# xenguon.net
KiCad netlist of a schematic drawn in Altium Designer
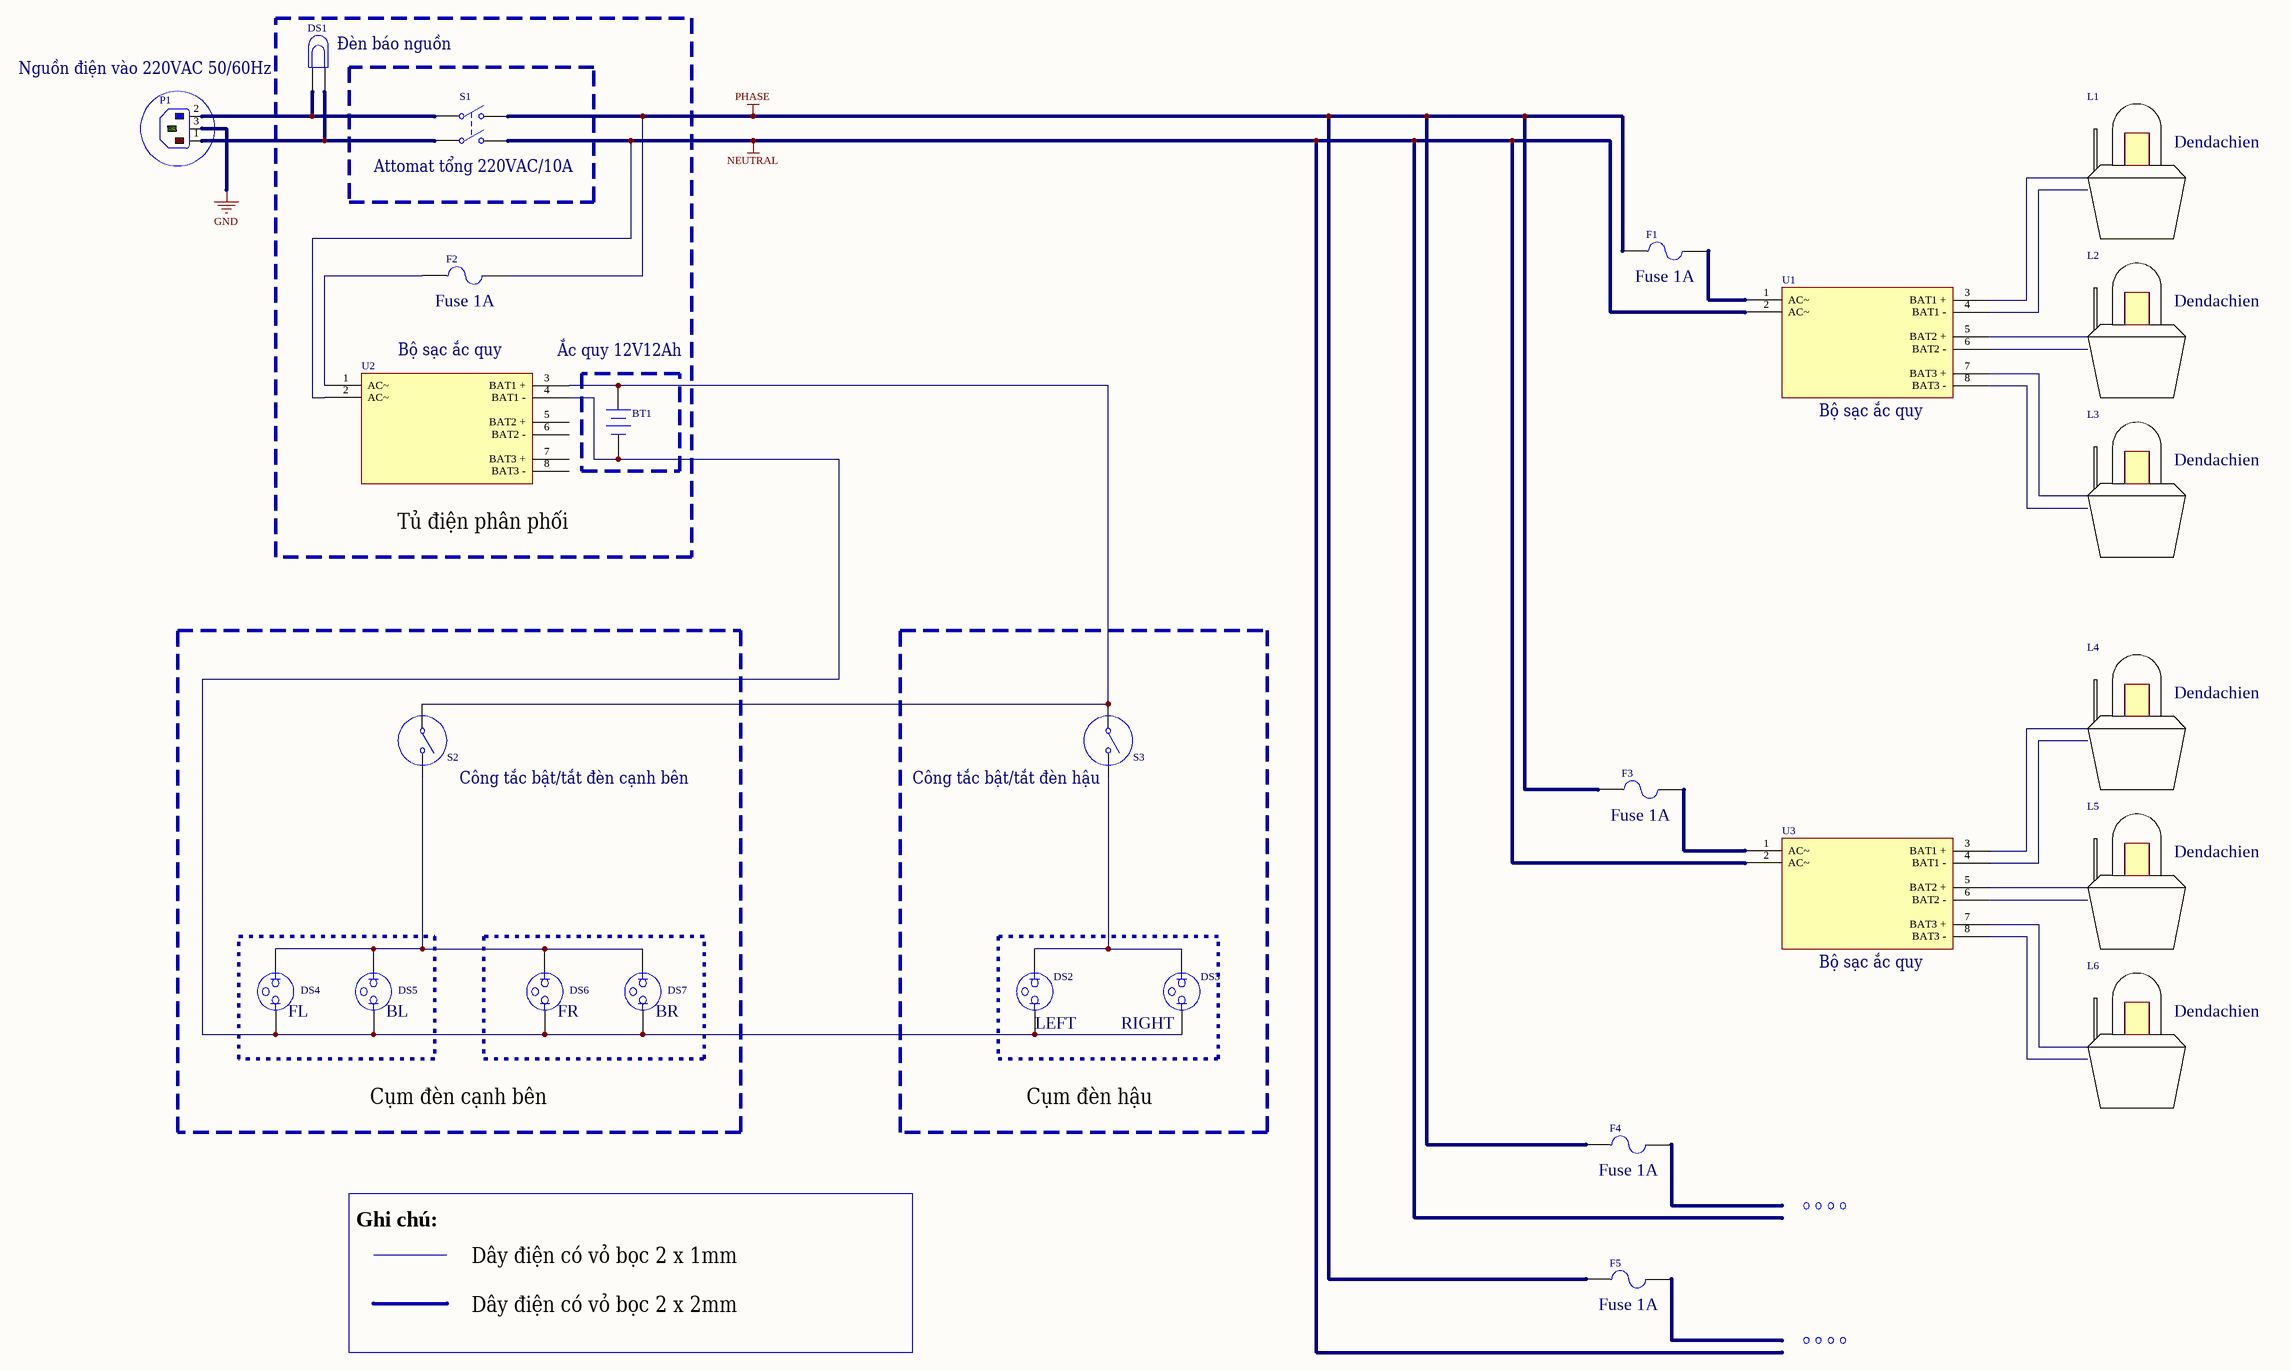
[diagram p0: xenguon.SchDoc]

(export (version "E")
  (design (tool "Eeschema 10.0.6"))
  (components
    (comp (ref "BT1")
      (value "Ắc quy 12V12Ah")
      (footprint "BAT-2")
      (description "Multicell Battery")
      (fields (field (name "PUBLISHER") "Altium Limited"))
      (libsource (lib "Miscellaneous Devices") (part "Battery"))
    )
    (comp (ref "DS1")
      (value "Đèn báo nguồn")
      (footprint "PIN2")
      (description "Incandescent Bulb")
      (fields (field (name "PUBLISHER") "Altium Limited"))
      (libsource (lib "Miscellaneous Devices") (part "Lamp"))
    )
    (comp (ref "DS2")
      (value "LEFT")
      (footprint "PIN2")
      (description "Neon Lamp")
      (fields (field (name "PUBLISHER") "Altium Limited"))
      (libsource (lib "Miscellaneous Devices") (part "Lamp Neon"))
    )
    (comp (ref "DS3")
      (value "RIGHT")
      (footprint "PIN2")
      (description "Neon Lamp")
      (fields (field (name "PUBLISHER") "Altium Limited"))
      (libsource (lib "Miscellaneous Devices") (part "Lamp Neon"))
    )
    (comp (ref "DS4")
      (value "FL")
      (footprint "PIN2")
      (description "Neon Lamp")
      (fields (field (name "PUBLISHER") "Altium Limited"))
      (libsource (lib "Miscellaneous Devices") (part "Lamp Neon"))
    )
    (comp (ref "DS5")
      (value "BL")
      (footprint "PIN2")
      (description "Neon Lamp")
      (fields (field (name "PUBLISHER") "Altium Limited"))
      (libsource (lib "Miscellaneous Devices") (part "Lamp Neon"))
    )
    (comp (ref "DS6")
      (value "FR")
      (footprint "PIN2")
      (description "Neon Lamp")
      (fields (field (name "PUBLISHER") "Altium Limited"))
      (libsource (lib "Miscellaneous Devices") (part "Lamp Neon"))
    )
    (comp (ref "DS7")
      (value "BR")
      (footprint "PIN2")
      (description "Neon Lamp")
      (fields (field (name "PUBLISHER") "Altium Limited"))
      (libsource (lib "Miscellaneous Devices") (part "Lamp Neon"))
    )
    (comp (ref "F1")
      (value "Fuse 1A")
      (footprint "PIN-W2/E2.8")
      (description "Fuse")
      (fields (field (name "PUBLISHER") "Altium Limited"))
      (libsource (lib "Miscellaneous Devices") (part "Fuse 2"))
    )
    (comp (ref "F2")
      (value "Fuse 1A")
      (footprint "PIN-W2/E2.8")
      (description "Fuse")
      (fields (field (name "PUBLISHER") "Altium Limited"))
      (libsource (lib "Miscellaneous Devices") (part "Fuse 2"))
    )
    (comp (ref "F3")
      (value "Fuse 1A")
      (footprint "PIN-W2/E2.8")
      (description "Fuse")
      (fields (field (name "PUBLISHER") "Altium Limited"))
      (libsource (lib "Miscellaneous Devices") (part "Fuse 2"))
    )
    (comp (ref "F4")
      (value "Fuse 1A")
      (footprint "PIN-W2/E2.8")
      (description "Fuse")
      (fields (field (name "PUBLISHER") "Altium Limited"))
      (libsource (lib "Miscellaneous Devices") (part "Fuse 2"))
    )
    (comp (ref "F5")
      (value "Fuse 1A")
      (footprint "PIN-W2/E2.8")
      (description "Fuse")
      (fields (field (name "PUBLISHER") "Altium Limited"))
      (libsource (lib "Miscellaneous Devices") (part "Fuse 2"))
    )
    (comp (ref "L1") (value "Dendachien") (libsource (lib "DnsSchLib") (part "Dendachien")))
    (comp (ref "L2") (value "Dendachien") (libsource (lib "DnsSchLib") (part "Dendachien")))
    (comp (ref "L3") (value "Dendachien") (libsource (lib "DnsSchLib") (part "Dendachien")))
    (comp (ref "L4") (value "Dendachien") (libsource (lib "DnsSchLib") (part "Dendachien")))
    (comp (ref "L5") (value "Dendachien") (libsource (lib "DnsSchLib") (part "Dendachien")))
    (comp (ref "L6") (value "Dendachien") (libsource (lib "DnsSchLib") (part "Dendachien")))
    (comp (ref "P1")
      (value "Nguồn điện vào 220VAC 50/60Hz")
      (footprint "IEC9.14-2H3")
      (description "IEC Mains Power Inlet, EN60 320-1 C14 Class I Cold Condition, PC Flange Rear Mount, Chassis Plug")
      (fields (field (name "PUBLISHER") "Altium Limited"))
      (libsource (lib "Miscellaneous Connectors") (part "Plug AC Male"))
    )
    (comp (ref "S1")
      (value "Attomat tổng 220VAC/10A")
      (footprint "DPST-4")
      (description "Double-Pole, Single-Throw Switch")
      (fields (field (name "PUBLISHER") "Altium Limited"))
      (libsource (lib "Miscellaneous Devices") (part "SW-DPST"))
    )
    (comp (ref "S2")
      (value "Công tắc bật/tắt đèn cạnh bên")
      (footprint "SPST-2")
      (description "Single-Pole, Single-Throw Switch")
      (fields (field (name "PUBLISHER") "Altium Limited"))
      (libsource (lib "Miscellaneous Devices") (part "SW-SPST"))
    )
    (comp (ref "S3")
      (value "Công tắc bật/tắt đèn hậu")
      (footprint "SPST-2")
      (description "Single-Pole, Single-Throw Switch")
      (fields (field (name "PUBLISHER") "Altium Limited"))
      (libsource (lib "Miscellaneous Devices") (part "SW-SPST"))
    )
    (comp (ref "U1") (value "Bộ sạc ắc quy") (libsource (lib "DnsSchLib") (part "Bosacacquy")))
    (comp (ref "U2") (value "Bộ sạc ắc quy") (libsource (lib "DnsSchLib") (part "Bosacacquy")))
    (comp (ref "U3") (value "Bộ sạc ắc quy") (libsource (lib "DnsSchLib") (part "Bosacacquy")))
  )
  (nets
    (net (code "1") (name "GND") (class "Default")
      (node (ref "P1") (pin "3") (pinfunction "E_3") (pintype "power_in"))
    )
    (net (code "2") (name "NEUTRAL") (class "Default")
      (node (ref "S1") (pin "4") (pinfunction "NO2_4") (pintype "passive"))
      (node (ref "U1") (pin "2") (pinfunction "AC~_2") (pintype "passive"))
      (node (ref "U2") (pin "2") (pinfunction "AC~_2") (pintype "passive"))
      (node (ref "U3") (pin "2") (pinfunction "AC~_2") (pintype "passive"))
    )
    (net (code "3") (name "Net-(BT1-+)") (class "Default")
      (node (ref "BT1") (pin "1") (pinfunction "+_1") (pintype "passive"))
      (node (ref "S2") (pin "1") (pinfunction "COMMON_1") (pintype "passive"))
      (node (ref "S3") (pin "1") (pinfunction "COMMON_1") (pintype "passive"))
      (node (ref "U2") (pin "3") (pinfunction "BAT1_+_3") (pintype "passive"))
    )
    (net (code "4") (name "Net-(BT1--)") (class "Default")
      (node (ref "BT1") (pin "2") (pinfunction "-_2") (pintype "passive"))
      (node (ref "DS2") (pin "1") (pinfunction "1_1") (pintype "passive"))
      (node (ref "DS3") (pin "1") (pinfunction "1_1") (pintype "passive"))
      (node (ref "DS4") (pin "1") (pinfunction "1_1") (pintype "passive"))
      (node (ref "DS5") (pin "1") (pinfunction "1_1") (pintype "passive"))
      (node (ref "DS6") (pin "1") (pinfunction "1_1") (pintype "passive"))
      (node (ref "DS7") (pin "1") (pinfunction "1_1") (pintype "passive"))
      (node (ref "U2") (pin "4") (pinfunction "BAT1_-_4") (pintype "passive"))
    )
    (net (code "5") (name "Net-(F1-Pad2)") (class "Default")
      (node (ref "F1") (pin "2") (pinfunction "2_2") (pintype "passive"))
      (node (ref "U1") (pin "1") (pinfunction "AC~_1") (pintype "passive"))
    )
    (net (code "6") (name "Net-(F2-Pad1)") (class "Default")
      (node (ref "F2") (pin "1") (pinfunction "1_1") (pintype "passive"))
      (node (ref "U2") (pin "1") (pinfunction "AC~_1") (pintype "passive"))
    )
    (net (code "7") (name "Net-(F3-Pad2)") (class "Default")
      (node (ref "F3") (pin "2") (pinfunction "2_2") (pintype "passive"))
      (node (ref "U3") (pin "1") (pinfunction "AC~_1") (pintype "passive"))
    )
    (net (code "8") (name "Net-(P1-L)") (class "Default")
      (node (ref "DS1") (pin "2") (pinfunction "2_2") (pintype "passive"))
      (node (ref "P1") (pin "1") (pinfunction "L_1") (pintype "power_in"))
      (node (ref "S1") (pin "3") (pinfunction "COMMON2_3") (pintype "passive"))
    )
    (net (code "9") (name "Net-(P1-N)") (class "Default")
      (node (ref "DS1") (pin "1") (pinfunction "1_1") (pintype "passive"))
      (node (ref "P1") (pin "2") (pinfunction "N_2") (pintype "power_in"))
      (node (ref "S1") (pin "1") (pinfunction "COMMON1_1") (pintype "passive"))
    )
    (net (code "10") (name "Net-(S2-NO)") (class "Default")
      (node (ref "DS4") (pin "2") (pinfunction "2_2") (pintype "passive"))
      (node (ref "DS5") (pin "2") (pinfunction "2_2") (pintype "passive"))
      (node (ref "DS6") (pin "2") (pinfunction "2_2") (pintype "passive"))
      (node (ref "DS7") (pin "2") (pinfunction "2_2") (pintype "passive"))
      (node (ref "S2") (pin "2") (pinfunction "NO_2") (pintype "passive"))
    )
    (net (code "11") (name "Net-(S3-NO)") (class "Default")
      (node (ref "DS2") (pin "2") (pinfunction "2_2") (pintype "passive"))
      (node (ref "DS3") (pin "2") (pinfunction "2_2") (pintype "passive"))
      (node (ref "S3") (pin "2") (pinfunction "NO_2") (pintype "passive"))
    )
    (net (code "12") (name "PHASE") (class "Default")
      (node (ref "F1") (pin "1") (pinfunction "1_1") (pintype "passive"))
      (node (ref "F2") (pin "2") (pinfunction "2_2") (pintype "passive"))
      (node (ref "F3") (pin "1") (pinfunction "1_1") (pintype "passive"))
      (node (ref "F4") (pin "1") (pinfunction "1_1") (pintype "passive"))
      (node (ref "F5") (pin "1") (pinfunction "1_1") (pintype "passive"))
      (node (ref "S1") (pin "2") (pinfunction "NO1_2") (pintype "passive"))
    )
    (net (code "13") (name "unconnected-(F4-Pad2)") (class "Default")
      (node (ref "F4") (pin "2") (pinfunction "2_2") (pintype "passive"))
    )
    (net (code "14") (name "unconnected-(F5-Pad2)") (class "Default")
      (node (ref "F5") (pin "2") (pinfunction "2_2") (pintype "passive"))
    )
    (net (code "15") (name "unconnected-(U1-BAT1_+-Pad3)") (class "Default")
      (node (ref "U1") (pin "3") (pinfunction "BAT1_+_3") (pintype "passive"))
    )
    (net (code "16") (name "unconnected-(U1-BAT1_--Pad4)") (class "Default")
      (node (ref "U1") (pin "4") (pinfunction "BAT1_-_4") (pintype "passive"))
    )
    (net (code "17") (name "unconnected-(U1-BAT2_+-Pad5)") (class "Default")
      (node (ref "U1") (pin "5") (pinfunction "BAT2_+_5") (pintype "passive"))
    )
    (net (code "18") (name "unconnected-(U1-BAT2_--Pad6)") (class "Default")
      (node (ref "U1") (pin "6") (pinfunction "BAT2_-_6") (pintype "passive"))
    )
    (net (code "19") (name "unconnected-(U1-BAT3_+-Pad7)") (class "Default")
      (node (ref "U1") (pin "7") (pinfunction "BAT3_+_7") (pintype "passive"))
    )
    (net (code "20") (name "unconnected-(U1-BAT3_--Pad8)") (class "Default")
      (node (ref "U1") (pin "8") (pinfunction "BAT3_-_8") (pintype "passive"))
    )
    (net (code "21") (name "unconnected-(U2-BAT2_+-Pad5)") (class "Default")
      (node (ref "U2") (pin "5") (pinfunction "BAT2_+_5") (pintype "passive"))
    )
    (net (code "22") (name "unconnected-(U2-BAT2_--Pad6)") (class "Default")
      (node (ref "U2") (pin "6") (pinfunction "BAT2_-_6") (pintype "passive"))
    )
    (net (code "23") (name "unconnected-(U2-BAT3_+-Pad7)") (class "Default")
      (node (ref "U2") (pin "7") (pinfunction "BAT3_+_7") (pintype "passive"))
    )
    (net (code "24") (name "unconnected-(U2-BAT3_--Pad8)") (class "Default")
      (node (ref "U2") (pin "8") (pinfunction "BAT3_-_8") (pintype "passive"))
    )
    (net (code "25") (name "unconnected-(U3-BAT1_+-Pad3)") (class "Default")
      (node (ref "U3") (pin "3") (pinfunction "BAT1_+_3") (pintype "passive"))
    )
    (net (code "26") (name "unconnected-(U3-BAT1_--Pad4)") (class "Default")
      (node (ref "U3") (pin "4") (pinfunction "BAT1_-_4") (pintype "passive"))
    )
    (net (code "27") (name "unconnected-(U3-BAT2_+-Pad5)") (class "Default")
      (node (ref "U3") (pin "5") (pinfunction "BAT2_+_5") (pintype "passive"))
    )
    (net (code "28") (name "unconnected-(U3-BAT2_--Pad6)") (class "Default")
      (node (ref "U3") (pin "6") (pinfunction "BAT2_-_6") (pintype "passive"))
    )
    (net (code "29") (name "unconnected-(U3-BAT3_+-Pad7)") (class "Default")
      (node (ref "U3") (pin "7") (pinfunction "BAT3_+_7") (pintype "passive"))
    )
    (net (code "30") (name "unconnected-(U3-BAT3_--Pad8)") (class "Default")
      (node (ref "U3") (pin "8") (pinfunction "BAT3_-_8") (pintype "passive"))
    )
  )
)
